# DAC.net
KiCad netlist of a schematic drawn in Altium Designer
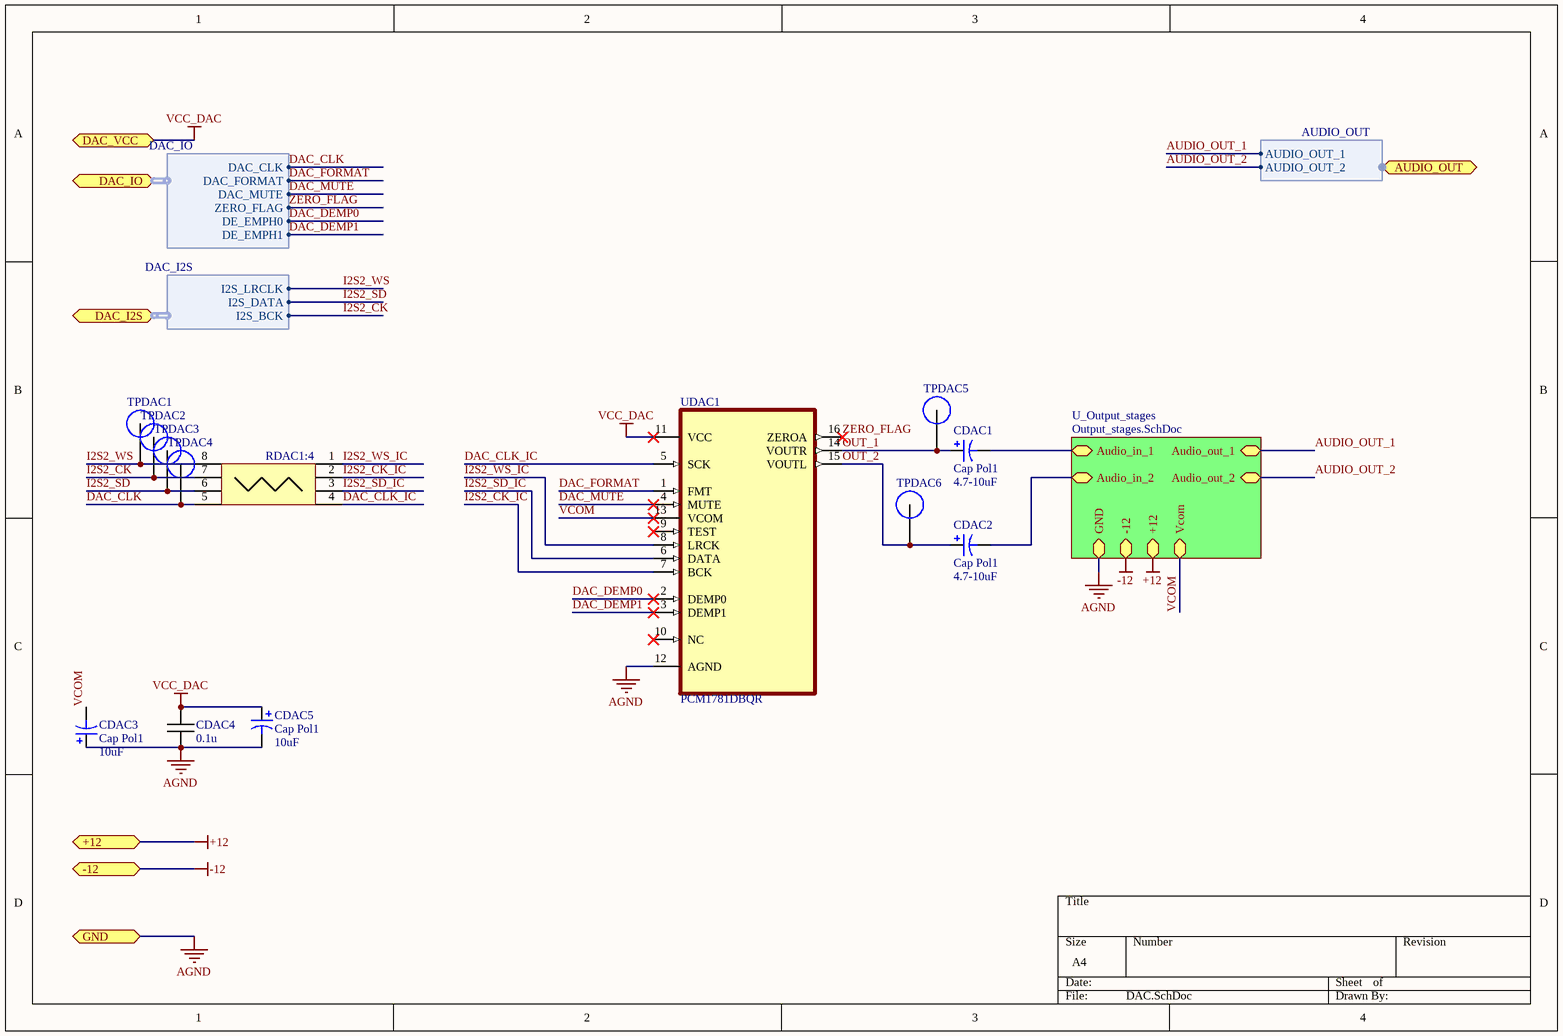
[diagram p0: DAC.SchDoc]

(export (version "E")
  (design (tool "Eeschema 10.0.6"))
  (components
    (comp (ref "CDAC1")
      (value "Cap Pol1")
      (footprint "C-RAD-4.5")
      (description "Polarized Capacitor (Radial)")
      (fields (field (name "ALTIUM_VALUE") "4.7-10uF") (field (name "PUBLISHER") "Altium Limited"))
      (libsource (lib "Miscellaneous Devices") (part "Cap Pol1"))
    )
    (comp (ref "CDAC2")
      (value "Cap Pol1")
      (footprint "C-RAD-4.5")
      (description "Polarized Capacitor (Radial)")
      (fields (field (name "ALTIUM_VALUE") "4.7-10uF") (field (name "PUBLISHER") "Altium Limited"))
      (libsource (lib "Miscellaneous Devices") (part "Cap Pol1"))
    )
    (comp (ref "CDAC3")
      (value "Cap Pol1")
      (footprint "C-RAD-4.5")
      (description "Polarized Capacitor (Radial)")
      (fields (field (name "ALTIUM_VALUE") "10uF") (field (name "PUBLISHER") "Altium Limited"))
      (libsource (lib "Miscellaneous Devices") (part "Cap Pol1"))
    )
    (comp (ref "CDAC4")
      (value "0.1u")
      (footprint "C 0603 / 1608")
      (libsource (lib "Standard") (part "Capacitor"))
    )
    (comp (ref "CDAC5")
      (value "Cap Pol1")
      (footprint "C-RAD-4.5")
      (description "Polarized Capacitor (Radial)")
      (fields (field (name "ALTIUM_VALUE") "10uF") (field (name "PUBLISHER") "Altium Limited"))
      (libsource (lib "Miscellaneous Devices") (part "Cap Pol1"))
    )
    (comp (ref "RDAC1:4")
      (value "742C083121JP")
      (footprint "RESARRAY(4x0603)")
      (fields (field (name "MF") "CTS Resistor"))
      (libsource (lib "Standard") (part "Resistor Array 4x"))
    )
    (comp (ref "TPDAC1")
      (value "Test Point")
      (footprint "Test POint")
      (libsource (lib "Standard") (part "Test Point"))
    )
    (comp (ref "TPDAC2")
      (value "Test Point")
      (footprint "Test POint")
      (libsource (lib "Standard") (part "Test Point"))
    )
    (comp (ref "TPDAC3")
      (value "Test Point")
      (footprint "Test POint")
      (libsource (lib "Standard") (part "Test Point"))
    )
    (comp (ref "TPDAC4")
      (value "Test Point")
      (footprint "Test POint")
      (libsource (lib "Standard") (part "Test Point"))
    )
    (comp (ref "TPDAC5")
      (value "Test Point")
      (footprint "Test POint")
      (libsource (lib "Standard") (part "Test Point"))
    )
    (comp (ref "TPDAC6")
      (value "Test Point")
      (footprint "Test POint")
      (libsource (lib "Standard") (part "Test Point"))
    )
    (comp (ref "UDAC1")
      (value "PCM1781DBQR")
      (footprint "SOP16-63P600X175-16N")
      (description "Converters - Digital to Analog _DAC_ 24-Bit, 192kHz, Ster Delta-Sig Audio DAC")
      (fields (field (name "MF") "Texas Instruments"))
      (libsource (lib "IC") (part "PCM1781DBQR"))
    )
  )
  (nets
    (net (code "8") (name "/Audio_in_1") (class "Default")
      (node (ref "CDAC1") (pin "2") (pinfunction "2_2") (pintype "passive"))
    )
    (net (code "9") (name "/Audio_in_2") (class "Default")
      (node (ref "CDAC2") (pin "2") (pinfunction "2_2") (pintype "passive"))
    )
    (net (code "10") (name "/DAC_CLK") (class "Default")
      (node (ref "RDAC1:4") (pin "5") (pinfunction "5_5") (pintype "passive"))
      (node (ref "TPDAC4") (pin "1") (pintype "passive"))
    )
    (net (code "11") (name "/DAC_CLK_IC") (class "Default")
      (node (ref "RDAC1:4") (pin "4") (pinfunction "4_4") (pintype "passive"))
      (node (ref "UDAC1") (pin "5") (pinfunction "SCK_5") (pintype "input"))
    )
    (net (code "12") (name "/DAC_DEMP0") (class "Default")
      (node (ref "UDAC1") (pin "2") (pinfunction "DEMP0_2") (pintype "input"))
    )
    (net (code "13") (name "/DAC_DEMP1") (class "Default")
      (node (ref "UDAC1") (pin "3") (pinfunction "DEMP1_3") (pintype "input"))
    )
    (net (code "14") (name "/DAC_FORMAT") (class "Default")
      (node (ref "UDAC1") (pin "1") (pinfunction "FMT_1") (pintype "input"))
    )
    (net (code "15") (name "/DAC_MUTE") (class "Default")
      (node (ref "UDAC1") (pin "4") (pinfunction "MUTE_4") (pintype "input"))
    )
    (net (code "16") (name "/I2S2_CK") (class "Default")
      (node (ref "RDAC1:4") (pin "7") (pinfunction "7_7") (pintype "passive"))
      (node (ref "TPDAC2") (pin "1") (pintype "passive"))
    )
    (net (code "17") (name "/I2S2_CK_IC") (class "Default")
      (node (ref "RDAC1:4") (pin "2") (pinfunction "2_2") (pintype "passive"))
      (node (ref "UDAC1") (pin "7") (pinfunction "BCK_7") (pintype "input"))
    )
    (net (code "18") (name "/I2S2_SD") (class "Default")
      (node (ref "RDAC1:4") (pin "6") (pinfunction "6_6") (pintype "passive"))
      (node (ref "TPDAC3") (pin "1") (pintype "passive"))
    )
    (net (code "19") (name "/I2S2_SD_IC") (class "Default")
      (node (ref "RDAC1:4") (pin "3") (pinfunction "3_3") (pintype "passive"))
      (node (ref "UDAC1") (pin "6") (pinfunction "DATA_6") (pintype "input"))
    )
    (net (code "20") (name "/I2S2_WS") (class "Default")
      (node (ref "RDAC1:4") (pin "8") (pinfunction "8_8") (pintype "passive"))
      (node (ref "TPDAC1") (pin "1") (pintype "passive"))
    )
    (net (code "21") (name "/I2S2_WS_IC") (class "Default")
      (node (ref "RDAC1:4") (pin "1") (pinfunction "1_1") (pintype "passive"))
      (node (ref "UDAC1") (pin "8") (pinfunction "LRCK_8") (pintype "input"))
    )
    (net (code "22") (name "/OUT_1") (class "Default")
      (node (ref "CDAC1") (pin "1") (pinfunction "1_1") (pintype "passive"))
      (node (ref "TPDAC5") (pin "1") (pintype "passive"))
      (node (ref "UDAC1") (pin "14") (pinfunction "VOUTR_14") (pintype "output"))
    )
    (net (code "23") (name "/OUT_2") (class "Default")
      (node (ref "CDAC2") (pin "1") (pinfunction "1_1") (pintype "passive"))
      (node (ref "TPDAC6") (pin "1") (pintype "passive"))
      (node (ref "UDAC1") (pin "15") (pinfunction "VOUTL_15") (pintype "output"))
    )
    (net (code "24") (name "/VCOM") (class "Default")
      (node (ref "CDAC3") (pin "2") (pinfunction "2_2") (pintype "passive"))
      (node (ref "UDAC1") (pin "13") (pinfunction "VCOM_13") (pintype "passive"))
    )
    (net (code "25") (name "/ZERO_FLAG") (class "Default")
      (node (ref "UDAC1") (pin "16") (pinfunction "ZEROA_16") (pintype "output"))
    )
    (net (code "29") (name "AGND") (class "Default")
      (node (ref "CDAC3") (pin "1") (pinfunction "1_1") (pintype "passive"))
      (node (ref "CDAC4") (pin "2") (pinfunction "1_2") (pintype "passive"))
      (node (ref "CDAC5") (pin "2") (pinfunction "2_2") (pintype "passive"))
      (node (ref "UDAC1") (pin "12") (pinfunction "AGND_12") (pintype "passive"))
    )
    (net (code "30") (name "VCC_DAC") (class "Default")
      (node (ref "CDAC4") (pin "1") (pinfunction "1_1") (pintype "passive"))
      (node (ref "CDAC5") (pin "1") (pinfunction "1_1") (pintype "passive"))
      (node (ref "UDAC1") (pin "11") (pinfunction "VCC_11") (pintype "power_in"))
    )
    (net (code "31") (name "unconnected-(UDAC1-NC-Pad10)") (class "Default")
      (node (ref "UDAC1") (pin "10") (pinfunction "NC_10") (pintype "input+no_connect"))
    )
    (net (code "32") (name "unconnected-(UDAC1-TEST-Pad9)") (class "Default")
      (node (ref "UDAC1") (pin "9") (pinfunction "TEST_9") (pintype "input+no_connect"))
    )
  )
)
